# Logic_in.net
KiCad netlist of a schematic drawn in Altium Designer
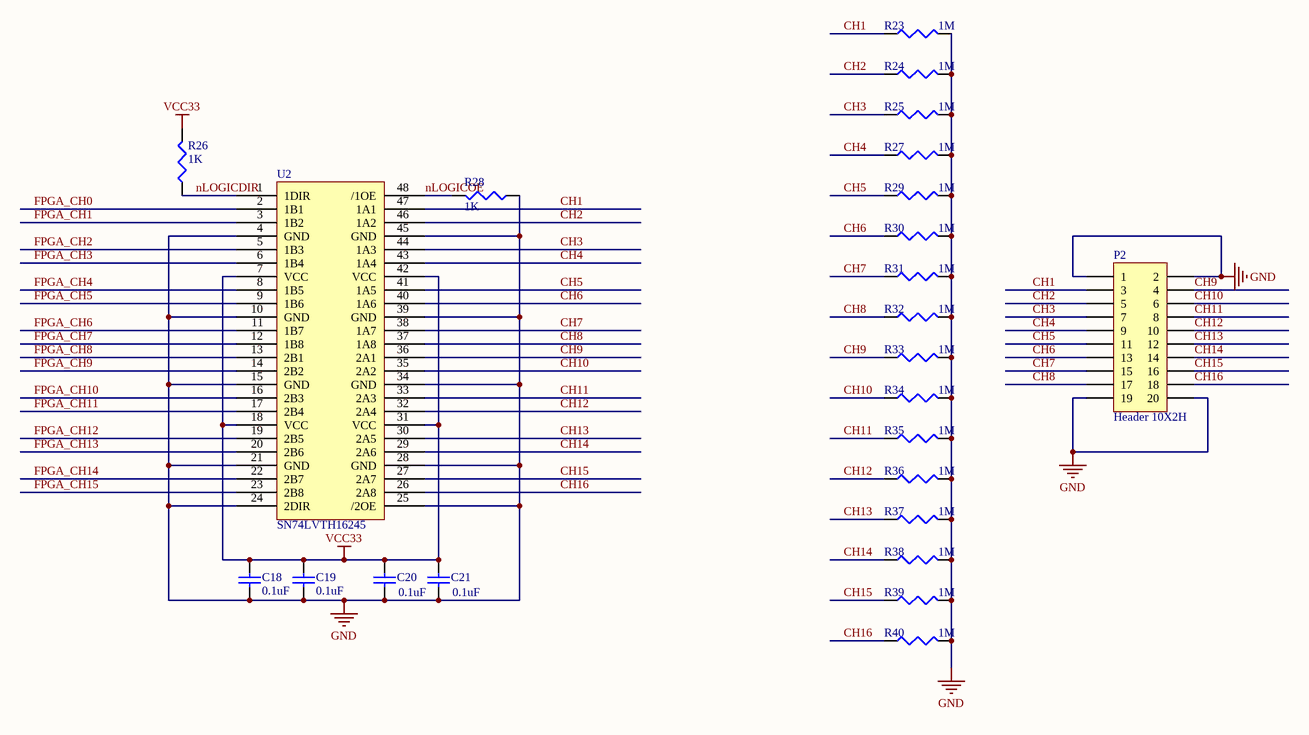
[diagram p0: Logic in.SchDoc]

(export (version "E")
  (design (tool "Eeschema 10.0.6"))
  (components
    (comp (ref "C18")
      (value "0.1uF")
      (footprint "cc0603")
      (description "Capacitor")
      (fields (field (name "PUBLISHER") "Altium Limited"))
      (libsource (lib "Miscellaneous Devices") (part "Cap"))
    )
    (comp (ref "C19")
      (value "0.1uF")
      (footprint "cc0603")
      (description "Capacitor")
      (fields (field (name "PUBLISHER") "Altium Limited"))
      (libsource (lib "Miscellaneous Devices") (part "Cap"))
    )
    (comp (ref "C20")
      (value "0.1uF")
      (footprint "cc0603")
      (description "Capacitor")
      (fields (field (name "PUBLISHER") "Altium Limited"))
      (libsource (lib "Miscellaneous Devices") (part "Cap"))
    )
    (comp (ref "C21")
      (value "0.1uF")
      (footprint "cc0603")
      (description "Capacitor")
      (fields (field (name "PUBLISHER") "Altium Limited"))
      (libsource (lib "Miscellaneous Devices") (part "Cap"))
    )
    (comp (ref "P2")
      (value "Header 10X2H")
      (footprint "HDR2X10")
      (description "Header, 10-Pin, Dual row, Right Angle")
      (fields (field (name "PUBLISHER") "Altium Limited"))
      (libsource (lib "Miscellaneous Connectors") (part "Header 10X2H"))
    )
    (comp (ref "R23")
      (value "1M")
      (footprint "CR0603")
      (description "Resistor")
      (fields (field (name "PUBLISHER") "Altium Limited"))
      (libsource (lib "Miscellaneous Devices") (part "Res3"))
    )
    (comp (ref "R24")
      (value "1M")
      (footprint "CR0603")
      (description "Resistor")
      (fields (field (name "PUBLISHER") "Altium Limited"))
      (libsource (lib "Miscellaneous Devices") (part "Res3"))
    )
    (comp (ref "R25")
      (value "1M")
      (footprint "CR0603")
      (description "Resistor")
      (fields (field (name "PUBLISHER") "Altium Limited"))
      (libsource (lib "Miscellaneous Devices") (part "Res3"))
    )
    (comp (ref "R26")
      (value "1K")
      (footprint "CR0603")
      (description "Resistor")
      (fields (field (name "PUBLISHER") "Altium Limited"))
      (libsource (lib "Miscellaneous Devices") (part "Res3"))
    )
    (comp (ref "R27")
      (value "1M")
      (footprint "CR0603")
      (description "Resistor")
      (fields (field (name "PUBLISHER") "Altium Limited"))
      (libsource (lib "Miscellaneous Devices") (part "Res3"))
    )
    (comp (ref "R28")
      (value "1K")
      (footprint "CR0603")
      (description "Resistor")
      (fields (field (name "PUBLISHER") "Altium Limited"))
      (libsource (lib "Miscellaneous Devices") (part "Res3"))
    )
    (comp (ref "R29")
      (value "1M")
      (footprint "CR0603")
      (description "Resistor")
      (fields (field (name "PUBLISHER") "Altium Limited"))
      (libsource (lib "Miscellaneous Devices") (part "Res3"))
    )
    (comp (ref "R30")
      (value "1M")
      (footprint "CR0603")
      (description "Resistor")
      (fields (field (name "PUBLISHER") "Altium Limited"))
      (libsource (lib "Miscellaneous Devices") (part "Res3"))
    )
    (comp (ref "R31")
      (value "1M")
      (footprint "CR0603")
      (description "Resistor")
      (fields (field (name "PUBLISHER") "Altium Limited"))
      (libsource (lib "Miscellaneous Devices") (part "Res3"))
    )
    (comp (ref "R32")
      (value "1M")
      (footprint "CR0603")
      (description "Resistor")
      (fields (field (name "PUBLISHER") "Altium Limited"))
      (libsource (lib "Miscellaneous Devices") (part "Res3"))
    )
    (comp (ref "R33")
      (value "1M")
      (footprint "CR0603")
      (description "Resistor")
      (fields (field (name "PUBLISHER") "Altium Limited"))
      (libsource (lib "Miscellaneous Devices") (part "Res3"))
    )
    (comp (ref "R34")
      (value "1M")
      (footprint "CR0603")
      (description "Resistor")
      (fields (field (name "PUBLISHER") "Altium Limited"))
      (libsource (lib "Miscellaneous Devices") (part "Res3"))
    )
    (comp (ref "R35")
      (value "1M")
      (footprint "CR0603")
      (description "Resistor")
      (fields (field (name "PUBLISHER") "Altium Limited"))
      (libsource (lib "Miscellaneous Devices") (part "Res3"))
    )
    (comp (ref "R36")
      (value "1M")
      (footprint "CR0603")
      (description "Resistor")
      (fields (field (name "PUBLISHER") "Altium Limited"))
      (libsource (lib "Miscellaneous Devices") (part "Res3"))
    )
    (comp (ref "R37")
      (value "1M")
      (footprint "CR0603")
      (description "Resistor")
      (fields (field (name "PUBLISHER") "Altium Limited"))
      (libsource (lib "Miscellaneous Devices") (part "Res3"))
    )
    (comp (ref "R38")
      (value "1M")
      (footprint "CR0603")
      (description "Resistor")
      (fields (field (name "PUBLISHER") "Altium Limited"))
      (libsource (lib "Miscellaneous Devices") (part "Res3"))
    )
    (comp (ref "R39")
      (value "1M")
      (footprint "CR0603")
      (description "Resistor")
      (fields (field (name "PUBLISHER") "Altium Limited"))
      (libsource (lib "Miscellaneous Devices") (part "Res3"))
    )
    (comp (ref "R40")
      (value "1M")
      (footprint "CR0603")
      (description "Resistor")
      (fields (field (name "PUBLISHER") "Altium Limited"))
      (libsource (lib "Miscellaneous Devices") (part "Res3"))
    )
    (comp (ref "U2")
      (value "SN74LVTH16245")
      (footprint "SN74HC16245")
      (libsource (lib "CCD97") (part "SN74LVTH16245"))
    )
  )
  (nets
    (net (code "1") (name "/CH1") (class "Default")
      (node (ref "P2") (pin "3") (pinfunction "3_3") (pintype "passive"))
      (node (ref "R23") (pin "1") (pinfunction "1_1") (pintype "passive"))
      (node (ref "U2") (pin "47") (pinfunction "1A1_47") (pintype "passive"))
    )
    (net (code "2") (name "/CH2") (class "Default")
      (node (ref "P2") (pin "5") (pinfunction "5_5") (pintype "passive"))
      (node (ref "R24") (pin "1") (pinfunction "1_1") (pintype "passive"))
      (node (ref "U2") (pin "46") (pinfunction "1A2_46") (pintype "passive"))
    )
    (net (code "3") (name "/CH3") (class "Default")
      (node (ref "P2") (pin "7") (pinfunction "7_7") (pintype "passive"))
      (node (ref "R25") (pin "1") (pinfunction "1_1") (pintype "passive"))
      (node (ref "U2") (pin "44") (pinfunction "1A3_44") (pintype "passive"))
    )
    (net (code "4") (name "/CH4") (class "Default")
      (node (ref "P2") (pin "9") (pinfunction "9_9") (pintype "passive"))
      (node (ref "R27") (pin "1") (pinfunction "1_1") (pintype "passive"))
      (node (ref "U2") (pin "43") (pinfunction "1A4_43") (pintype "passive"))
    )
    (net (code "5") (name "/CH5") (class "Default")
      (node (ref "P2") (pin "11") (pinfunction "11_11") (pintype "passive"))
      (node (ref "R29") (pin "1") (pinfunction "1_1") (pintype "passive"))
      (node (ref "U2") (pin "41") (pinfunction "1A5_41") (pintype "passive"))
    )
    (net (code "6") (name "/CH6") (class "Default")
      (node (ref "P2") (pin "13") (pinfunction "13_13") (pintype "passive"))
      (node (ref "R30") (pin "1") (pinfunction "1_1") (pintype "passive"))
      (node (ref "U2") (pin "40") (pinfunction "1A6_40") (pintype "passive"))
    )
    (net (code "7") (name "/CH7") (class "Default")
      (node (ref "P2") (pin "15") (pinfunction "15_15") (pintype "passive"))
      (node (ref "R31") (pin "1") (pinfunction "1_1") (pintype "passive"))
      (node (ref "U2") (pin "38") (pinfunction "1A7_38") (pintype "passive"))
    )
    (net (code "8") (name "/CH8") (class "Default")
      (node (ref "P2") (pin "17") (pinfunction "17_17") (pintype "passive"))
      (node (ref "R32") (pin "1") (pinfunction "1_1") (pintype "passive"))
      (node (ref "U2") (pin "37") (pinfunction "1A8_37") (pintype "passive"))
    )
    (net (code "9") (name "/CH9") (class "Default")
      (node (ref "P2") (pin "4") (pinfunction "4_4") (pintype "passive"))
      (node (ref "R33") (pin "1") (pinfunction "1_1") (pintype "passive"))
      (node (ref "U2") (pin "36") (pinfunction "2A1_36") (pintype "passive"))
    )
    (net (code "10") (name "/CH10") (class "Default")
      (node (ref "P2") (pin "6") (pinfunction "6_6") (pintype "passive"))
      (node (ref "R34") (pin "1") (pinfunction "1_1") (pintype "passive"))
      (node (ref "U2") (pin "35") (pinfunction "2A2_35") (pintype "passive"))
    )
    (net (code "11") (name "/CH11") (class "Default")
      (node (ref "P2") (pin "8") (pinfunction "8_8") (pintype "passive"))
      (node (ref "R35") (pin "1") (pinfunction "1_1") (pintype "passive"))
      (node (ref "U2") (pin "33") (pinfunction "2A3_33") (pintype "passive"))
    )
    (net (code "12") (name "/CH12") (class "Default")
      (node (ref "P2") (pin "10") (pinfunction "10_10") (pintype "passive"))
      (node (ref "R36") (pin "1") (pinfunction "1_1") (pintype "passive"))
      (node (ref "U2") (pin "32") (pinfunction "2A4_32") (pintype "passive"))
    )
    (net (code "13") (name "/CH13") (class "Default")
      (node (ref "P2") (pin "12") (pinfunction "12_12") (pintype "passive"))
      (node (ref "R37") (pin "1") (pinfunction "1_1") (pintype "passive"))
      (node (ref "U2") (pin "30") (pinfunction "2A5_30") (pintype "passive"))
    )
    (net (code "14") (name "/CH14") (class "Default")
      (node (ref "P2") (pin "14") (pinfunction "14_14") (pintype "passive"))
      (node (ref "R38") (pin "1") (pinfunction "1_1") (pintype "passive"))
      (node (ref "U2") (pin "29") (pinfunction "2A6_29") (pintype "passive"))
    )
    (net (code "15") (name "/CH15") (class "Default")
      (node (ref "P2") (pin "16") (pinfunction "16_16") (pintype "passive"))
      (node (ref "R39") (pin "1") (pinfunction "1_1") (pintype "passive"))
      (node (ref "U2") (pin "27") (pinfunction "2A7_27") (pintype "passive"))
    )
    (net (code "16") (name "/CH16") (class "Default")
      (node (ref "P2") (pin "18") (pinfunction "18_18") (pintype "passive"))
      (node (ref "R40") (pin "1") (pinfunction "1_1") (pintype "passive"))
      (node (ref "U2") (pin "26") (pinfunction "2A8_26") (pintype "passive"))
    )
    (net (code "17") (name "/FPGA_CH0") (class "Default")
      (node (ref "U2") (pin "2") (pinfunction "1B1_2") (pintype "passive"))
    )
    (net (code "18") (name "/FPGA_CH1") (class "Default")
      (node (ref "U2") (pin "3") (pinfunction "1B2_3") (pintype "passive"))
    )
    (net (code "19") (name "/FPGA_CH2") (class "Default")
      (node (ref "U2") (pin "5") (pinfunction "1B3_5") (pintype "passive"))
    )
    (net (code "20") (name "/FPGA_CH3") (class "Default")
      (node (ref "U2") (pin "6") (pinfunction "1B4_6") (pintype "passive"))
    )
    (net (code "21") (name "/FPGA_CH4") (class "Default")
      (node (ref "U2") (pin "8") (pinfunction "1B5_8") (pintype "passive"))
    )
    (net (code "22") (name "/FPGA_CH5") (class "Default")
      (node (ref "U2") (pin "9") (pinfunction "1B6_9") (pintype "passive"))
    )
    (net (code "23") (name "/FPGA_CH6") (class "Default")
      (node (ref "U2") (pin "11") (pinfunction "1B7_11") (pintype "passive"))
    )
    (net (code "24") (name "/FPGA_CH7") (class "Default")
      (node (ref "U2") (pin "12") (pinfunction "1B8_12") (pintype "passive"))
    )
    (net (code "25") (name "/FPGA_CH8") (class "Default")
      (node (ref "U2") (pin "13") (pinfunction "2B1_13") (pintype "passive"))
    )
    (net (code "26") (name "/FPGA_CH9") (class "Default")
      (node (ref "U2") (pin "14") (pinfunction "2B2_14") (pintype "passive"))
    )
    (net (code "27") (name "/FPGA_CH10") (class "Default")
      (node (ref "U2") (pin "16") (pinfunction "2B3_16") (pintype "passive"))
    )
    (net (code "28") (name "/FPGA_CH11") (class "Default")
      (node (ref "U2") (pin "17") (pinfunction "2B4_17") (pintype "passive"))
    )
    (net (code "29") (name "/FPGA_CH12") (class "Default")
      (node (ref "U2") (pin "19") (pinfunction "2B5_19") (pintype "passive"))
    )
    (net (code "30") (name "/FPGA_CH13") (class "Default")
      (node (ref "U2") (pin "20") (pinfunction "2B6_20") (pintype "passive"))
    )
    (net (code "31") (name "/FPGA_CH14") (class "Default")
      (node (ref "U2") (pin "22") (pinfunction "2B7_22") (pintype "passive"))
    )
    (net (code "32") (name "/FPGA_CH15") (class "Default")
      (node (ref "U2") (pin "23") (pinfunction "2B8_23") (pintype "passive"))
    )
    (net (code "33") (name "/nLOGICDIR") (class "Default")
      (node (ref "R26") (pin "1") (pinfunction "1_1") (pintype "passive"))
      (node (ref "U2") (pin "1") (pinfunction "1DIR_1") (pintype "passive"))
    )
    (net (code "34") (name "/nLOGICOE") (class "Default")
      (node (ref "R28") (pin "2") (pinfunction "2_2") (pintype "passive"))
      (node (ref "U2") (pin "48") (pinfunction "/1OE_48") (pintype "passive"))
    )
    (net (code "35") (name "GND") (class "Default")
      (node (ref "C18") (pin "2") (pinfunction "2_2") (pintype "passive"))
      (node (ref "C19") (pin "2") (pinfunction "2_2") (pintype "passive"))
      (node (ref "C20") (pin "1") (pinfunction "1_1") (pintype "passive"))
      (node (ref "C21") (pin "1") (pinfunction "1_1") (pintype "passive"))
      (node (ref "P2") (pin "1") (pinfunction "1_1") (pintype "passive"))
      (node (ref "P2") (pin "19") (pinfunction "19_19") (pintype "passive"))
      (node (ref "P2") (pin "2") (pinfunction "2_2") (pintype "passive"))
      (node (ref "P2") (pin "20") (pinfunction "20_20") (pintype "passive"))
      (node (ref "R23") (pin "2") (pinfunction "2_2") (pintype "passive"))
      (node (ref "R24") (pin "2") (pinfunction "2_2") (pintype "passive"))
      (node (ref "R25") (pin "2") (pinfunction "2_2") (pintype "passive"))
      (node (ref "R27") (pin "2") (pinfunction "2_2") (pintype "passive"))
      (node (ref "R28") (pin "1") (pinfunction "1_1") (pintype "passive"))
      (node (ref "R29") (pin "2") (pinfunction "2_2") (pintype "passive"))
      (node (ref "R30") (pin "2") (pinfunction "2_2") (pintype "passive"))
      (node (ref "R31") (pin "2") (pinfunction "2_2") (pintype "passive"))
      (node (ref "R32") (pin "2") (pinfunction "2_2") (pintype "passive"))
      (node (ref "R33") (pin "2") (pinfunction "2_2") (pintype "passive"))
      (node (ref "R34") (pin "2") (pinfunction "2_2") (pintype "passive"))
      (node (ref "R35") (pin "2") (pinfunction "2_2") (pintype "passive"))
      (node (ref "R36") (pin "2") (pinfunction "2_2") (pintype "passive"))
      (node (ref "R37") (pin "2") (pinfunction "2_2") (pintype "passive"))
      (node (ref "R38") (pin "2") (pinfunction "2_2") (pintype "passive"))
      (node (ref "R39") (pin "2") (pinfunction "2_2") (pintype "passive"))
      (node (ref "R40") (pin "2") (pinfunction "2_2") (pintype "passive"))
      (node (ref "U2") (pin "10") (pinfunction "GND_10") (pintype "passive"))
      (node (ref "U2") (pin "15") (pinfunction "GND_15") (pintype "passive"))
      (node (ref "U2") (pin "21") (pinfunction "GND_21") (pintype "passive"))
      (node (ref "U2") (pin "24") (pinfunction "2DIR_24") (pintype "passive"))
      (node (ref "U2") (pin "25") (pinfunction "/2OE_25") (pintype "passive"))
      (node (ref "U2") (pin "28") (pinfunction "GND_28") (pintype "passive"))
      (node (ref "U2") (pin "34") (pinfunction "GND_34") (pintype "passive"))
      (node (ref "U2") (pin "39") (pinfunction "GND_39") (pintype "passive"))
      (node (ref "U2") (pin "4") (pinfunction "GND_4") (pintype "passive"))
      (node (ref "U2") (pin "45") (pinfunction "GND_45") (pintype "passive"))
    )
    (net (code "36") (name "VCC33") (class "Default")
      (node (ref "C18") (pin "1") (pinfunction "1_1") (pintype "passive"))
      (node (ref "C19") (pin "1") (pinfunction "1_1") (pintype "passive"))
      (node (ref "C20") (pin "2") (pinfunction "2_2") (pintype "passive"))
      (node (ref "C21") (pin "2") (pinfunction "2_2") (pintype "passive"))
      (node (ref "R26") (pin "2") (pinfunction "2_2") (pintype "passive"))
      (node (ref "U2") (pin "18") (pinfunction "VCC_18") (pintype "passive"))
      (node (ref "U2") (pin "31") (pinfunction "VCC_31") (pintype "passive"))
      (node (ref "U2") (pin "42") (pinfunction "VCC_42") (pintype "passive"))
      (node (ref "U2") (pin "7") (pinfunction "VCC_7") (pintype "passive"))
    )
  )
)
